# VR_78XX_1.net
KiCad netlist of a schematic drawn in EAGLE
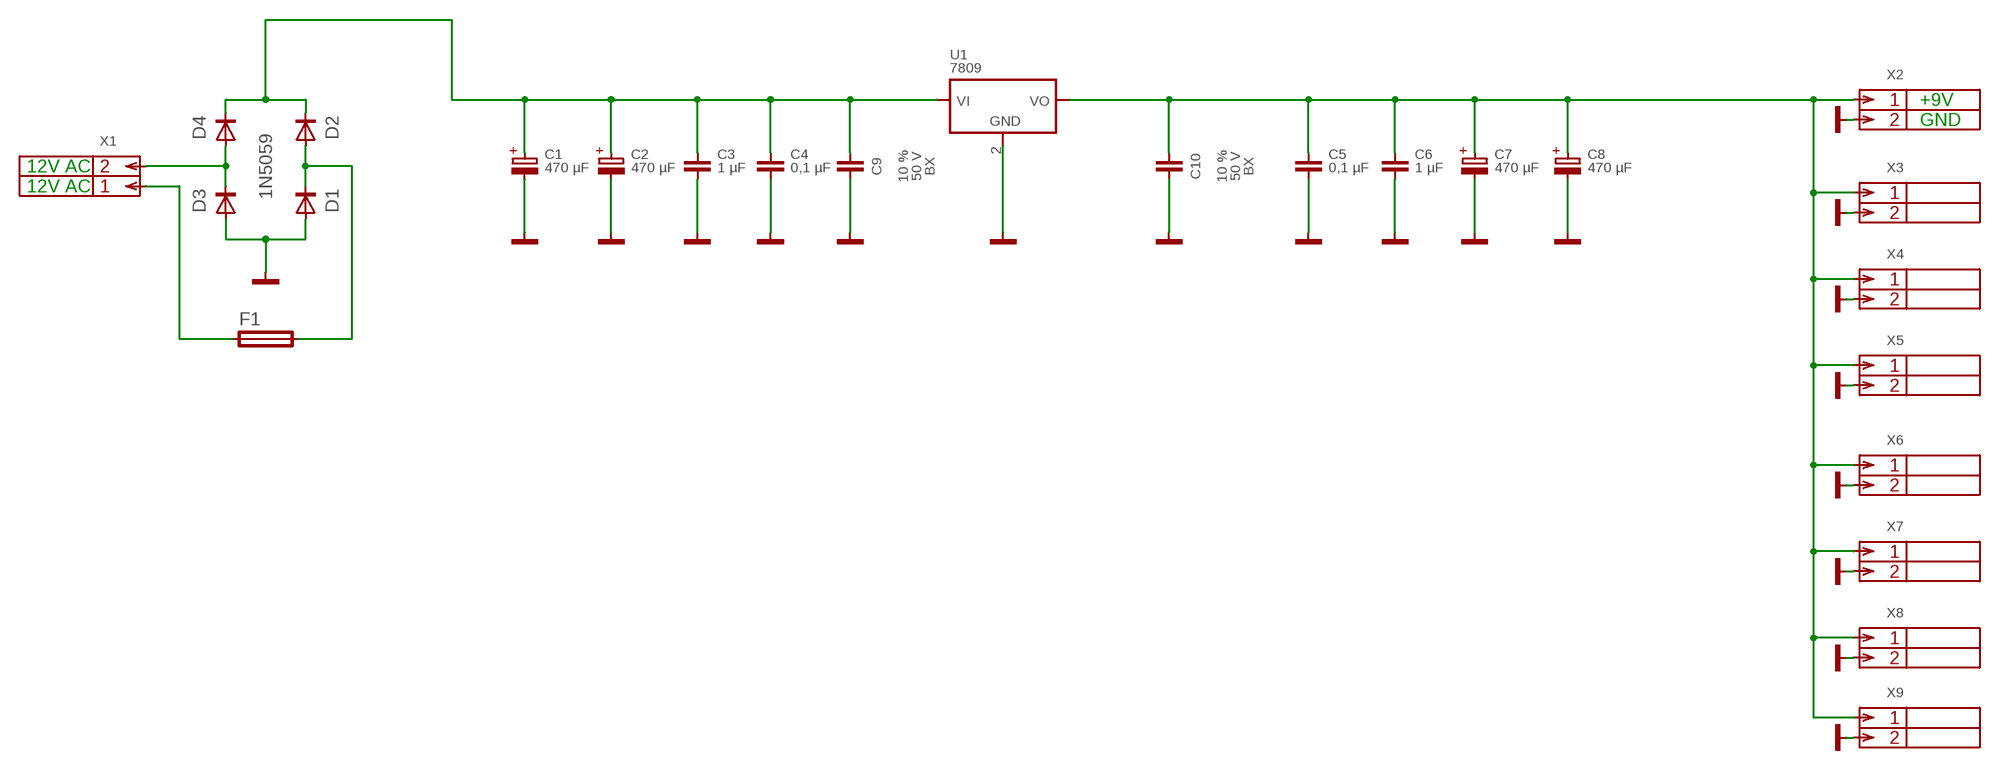
[diagram p0: schematic, sheet 1]

(export (version "E")
  (design (tool "Eeschema 10.0.6"))
  (components
    (comp (ref "C1")
      (value "470 µF")
      (footprint "eagle-import:BC10-30")
      (libsource (lib "eagle-import") (part "BEYSHLAG-118AHT0"))
    )
    (comp (ref "C2")
      (value "470 µF")
      (footprint "eagle-import:BC10-30")
      (libsource (lib "eagle-import") (part "BEYSHLAG-118AHT0"))
    )
    (comp (ref "C3") (value "1 µF") (footprint "eagle-import:1") (libsource (lib "eagle-import") (part "1")))
    (comp (ref "C4")
      (value "0,1 µF")
      (footprint "eagle-import:0.1")
      (libsource (lib "eagle-import") (part "0.1"))
    )
    (comp (ref "C5")
      (value "0,1 µF")
      (footprint "eagle-import:0.1")
      (libsource (lib "eagle-import") (part "0.1"))
    )
    (comp (ref "C6") (value "1 µF") (footprint "eagle-import:1") (libsource (lib "eagle-import") (part "1")))
    (comp (ref "C7")
      (value "470 µF")
      (footprint "eagle-import:BC10-30")
      (libsource (lib "eagle-import") (part "BEYSHLAG-118AHT0"))
    )
    (comp (ref "C8")
      (value "470 µF")
      (footprint "eagle-import:BC10-30")
      (libsource (lib "eagle-import") (part "BEYSHLAG-118AHT0"))
    )
    (comp (ref "C9")
      (value "C-EU050-025X075")
      (footprint "eagle-import:C050-025X075")
      (fields (field (name "VOLTAGE") "50 V") (field (name "TOLERANCE") "10 %"))
      (libsource (lib "eagle-import") (part "C-EU050-025X075"))
    )
    (comp (ref "C10")
      (value "C-EU050-025X075")
      (footprint "eagle-import:C050-025X075")
      (fields (field (name "VOLTAGE") "50 V") (field (name "TOLERANCE") "10 %"))
      (libsource (lib "eagle-import") (part "C-EU050-025X075"))
    )
    (comp (ref "D1")
      (value "1N5059")
      (footprint "eagle-import:DO204-10")
      (libsource (lib "eagle-import") (part "1N5059"))
    )
    (comp (ref "D2")
      (value "1N5059")
      (footprint "eagle-import:DO204-10")
      (libsource (lib "eagle-import") (part "1N5059"))
    )
    (comp (ref "D3")
      (value "1N5059")
      (footprint "eagle-import:DO204-10")
      (libsource (lib "eagle-import") (part "1N5059"))
    )
    (comp (ref "D4")
      (value "1N5059")
      (footprint "eagle-import:DO204-10")
      (libsource (lib "eagle-import") (part "1N5059"))
    )
    (comp (ref "F1")
      (value "GSH15")
      (footprint "eagle-import:GSH15")
      (libsource (lib "eagle-import") (part "GSH15"))
    )
    (comp (ref "U1")
      (value "7809")
      (footprint "eagle-import:TO220H")
      (libsource (lib "eagle-import") (part "78T05"))
    )
    (comp (ref "X1")
      (value "AK100V5")
      (footprint "eagle-import:AK100-2V")
      (libsource (lib "eagle-import") (part "AK100V5"))
    )
    (comp (ref "X2")
      (value "MTA02-100")
      (footprint "eagle-import:10X02MTA")
      (libsource (lib "eagle-import") (part "MTA02-100"))
    )
    (comp (ref "X3")
      (value "MTA02-100")
      (footprint "eagle-import:10X02MTA")
      (libsource (lib "eagle-import") (part "MTA02-100"))
    )
    (comp (ref "X4")
      (value "MTA02-100")
      (footprint "eagle-import:10X02MTA")
      (libsource (lib "eagle-import") (part "MTA02-100"))
    )
    (comp (ref "X5")
      (value "MTA02-100")
      (footprint "eagle-import:10X02MTA")
      (libsource (lib "eagle-import") (part "MTA02-100"))
    )
    (comp (ref "X6")
      (value "MTA02-100")
      (footprint "eagle-import:10X02MTA")
      (libsource (lib "eagle-import") (part "MTA02-100"))
    )
    (comp (ref "X7")
      (value "MTA02-100")
      (footprint "eagle-import:10X02MTA")
      (libsource (lib "eagle-import") (part "MTA02-100"))
    )
    (comp (ref "X8")
      (value "MTA02-100")
      (footprint "eagle-import:10X02MTA")
      (libsource (lib "eagle-import") (part "MTA02-100"))
    )
    (comp (ref "X9")
      (value "MTA02-100")
      (footprint "eagle-import:10X02MTA")
      (libsource (lib "eagle-import") (part "MTA02-100"))
    )
  )
  (nets
    (net (code "1") (name "GND") (class "Default")
      (node (ref "C1") (pin "-") (pinfunction "-_-") (pintype "passive"))
      (node (ref "C10") (pin "2") (pinfunction "2_2") (pintype "passive"))
      (node (ref "C2") (pin "-") (pinfunction "-_-") (pintype "passive"))
      (node (ref "C3") (pin "2") (pinfunction "2_2") (pintype "passive"))
      (node (ref "C4") (pin "2") (pinfunction "2_2") (pintype "passive"))
      (node (ref "C5") (pin "2") (pinfunction "2_2") (pintype "passive"))
      (node (ref "C6") (pin "2") (pinfunction "2_2") (pintype "passive"))
      (node (ref "C7") (pin "-") (pinfunction "-_-") (pintype "passive"))
      (node (ref "C8") (pin "-") (pinfunction "-_-") (pintype "passive"))
      (node (ref "C9") (pin "2") (pinfunction "2_2") (pintype "passive"))
      (node (ref "D1") (pin "A") (pinfunction "A_A") (pintype "passive"))
      (node (ref "D3") (pin "A") (pinfunction "A_A") (pintype "passive"))
      (node (ref "U1") (pin "2") (pinfunction "GND_2") (pintype "passive"))
      (node (ref "X2") (pin "2") (pinfunction "2_2") (pintype "passive"))
      (node (ref "X3") (pin "2") (pinfunction "2_2") (pintype "passive"))
      (node (ref "X4") (pin "2") (pinfunction "2_2") (pintype "passive"))
      (node (ref "X5") (pin "2") (pinfunction "2_2") (pintype "passive"))
      (node (ref "X6") (pin "2") (pinfunction "2_2") (pintype "passive"))
      (node (ref "X7") (pin "2") (pinfunction "2_2") (pintype "passive"))
      (node (ref "X8") (pin "2") (pinfunction "2_2") (pintype "passive"))
      (node (ref "X9") (pin "2") (pinfunction "2_2") (pintype "passive"))
    )
    (net (code "2") (name "Net-(D1-PadC)") (class "Default")
      (node (ref "D1") (pin "C") (pinfunction "C_C") (pintype "passive"))
      (node (ref "D2") (pin "A") (pinfunction "A_A") (pintype "passive"))
      (node (ref "F1") (pin "2") (pinfunction "2_2") (pintype "passive"))
    )
    (net (code "3") (name "Net-(U1-VI)") (class "Default")
      (node (ref "C1") (pin "+") (pinfunction "+_+") (pintype "passive"))
      (node (ref "C2") (pin "+") (pinfunction "+_+") (pintype "passive"))
      (node (ref "C3") (pin "1") (pinfunction "1_1") (pintype "passive"))
      (node (ref "C4") (pin "1") (pinfunction "1_1") (pintype "passive"))
      (node (ref "C9") (pin "1") (pinfunction "1_1") (pintype "passive"))
      (node (ref "D2") (pin "C") (pinfunction "C_C") (pintype "passive"))
      (node (ref "D4") (pin "C") (pinfunction "C_C") (pintype "passive"))
      (node (ref "U1") (pin "1") (pinfunction "VI_1") (pintype "input"))
    )
    (net (code "4") (name "Net-(U1-VO)") (class "Default")
      (node (ref "C10") (pin "1") (pinfunction "1_1") (pintype "passive"))
      (node (ref "C5") (pin "1") (pinfunction "1_1") (pintype "passive"))
      (node (ref "C6") (pin "1") (pinfunction "1_1") (pintype "passive"))
      (node (ref "C7") (pin "+") (pinfunction "+_+") (pintype "passive"))
      (node (ref "C8") (pin "+") (pinfunction "+_+") (pintype "passive"))
      (node (ref "U1") (pin "3") (pinfunction "VO_3") (pintype "passive"))
      (node (ref "X2") (pin "1") (pinfunction "1_1") (pintype "passive"))
      (node (ref "X3") (pin "1") (pinfunction "1_1") (pintype "passive"))
      (node (ref "X4") (pin "1") (pinfunction "1_1") (pintype "passive"))
      (node (ref "X5") (pin "1") (pinfunction "1_1") (pintype "passive"))
      (node (ref "X6") (pin "1") (pinfunction "1_1") (pintype "passive"))
      (node (ref "X7") (pin "1") (pinfunction "1_1") (pintype "passive"))
      (node (ref "X8") (pin "1") (pinfunction "1_1") (pintype "passive"))
      (node (ref "X9") (pin "1") (pinfunction "1_1") (pintype "passive"))
    )
    (net (code "5") (name "Net-(X1-1)") (class "Default")
      (node (ref "F1") (pin "1") (pinfunction "1_1") (pintype "passive"))
      (node (ref "X1") (pin "P$1") (pinfunction "1_P$1") (pintype "passive"))
    )
    (net (code "6") (name "Net-(X1-2)") (class "Default")
      (node (ref "D3") (pin "C") (pinfunction "C_C") (pintype "passive"))
      (node (ref "D4") (pin "A") (pinfunction "A_A") (pintype "passive"))
      (node (ref "X1") (pin "P$2") (pinfunction "2_P$2") (pintype "passive"))
    )
  )
)
